# Current_Sensor.net
KiCad netlist of a schematic drawn in Altium Designer
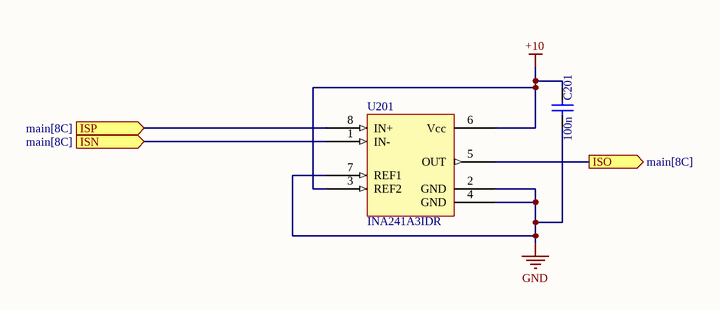
[diagram p0: Current_Sensor.SchDoc]

(export (version "E")
  (design (tool "Eeschema 10.0.6"))
  (components
    (comp (ref "C201")
      (value "100n")
      (footprint "CAP_1206")
      (description "Non Polarized Capacitor, SMD, 1206")
      (libsource (lib "Resistors and Capacitors") (part "CAPN 1206"))
    )
    (comp (ref "U201")
      (value "INA241A3IDR")
      (footprint "SOIC8_M")
      (description "Current Sense Amplifier 1 Circuit Single-Ended 8-SOIC")
      (libsource (lib "Projects_2025") (part "INA241A3IDR"))
    )
  )
  (nets
    (net (code "1") (name "+10") (class "Default")
      (node (ref "C201") (pin "2") (pinfunction "2_2") (pintype "passive"))
      (node (ref "U201") (pin "3") (pinfunction "REF2_3") (pintype "input"))
      (node (ref "U201") (pin "6") (pinfunction "Vcc_6") (pintype "power_in"))
    )
    (net (code "2") (name "/ISN") (class "Default")
      (node (ref "U201") (pin "1") (pinfunction "IN-_1") (pintype "input"))
    )
    (net (code "3") (name "/ISO") (class "Default")
      (node (ref "U201") (pin "5") (pinfunction "OUT_5") (pintype "output"))
    )
    (net (code "4") (name "/ISP") (class "Default")
      (node (ref "U201") (pin "8") (pinfunction "IN+_8") (pintype "input"))
    )
    (net (code "5") (name "GND") (class "Default")
      (node (ref "C201") (pin "1") (pinfunction "1_1") (pintype "passive"))
      (node (ref "U201") (pin "2") (pinfunction "GND_2") (pintype "power_in"))
      (node (ref "U201") (pin "4") (pinfunction "GND_4") (pintype "passive"))
      (node (ref "U201") (pin "7") (pinfunction "REF1_7") (pintype "input"))
    )
  )
)
